# ADC3_10M.net
KiCad netlist of a schematic drawn in EAGLE
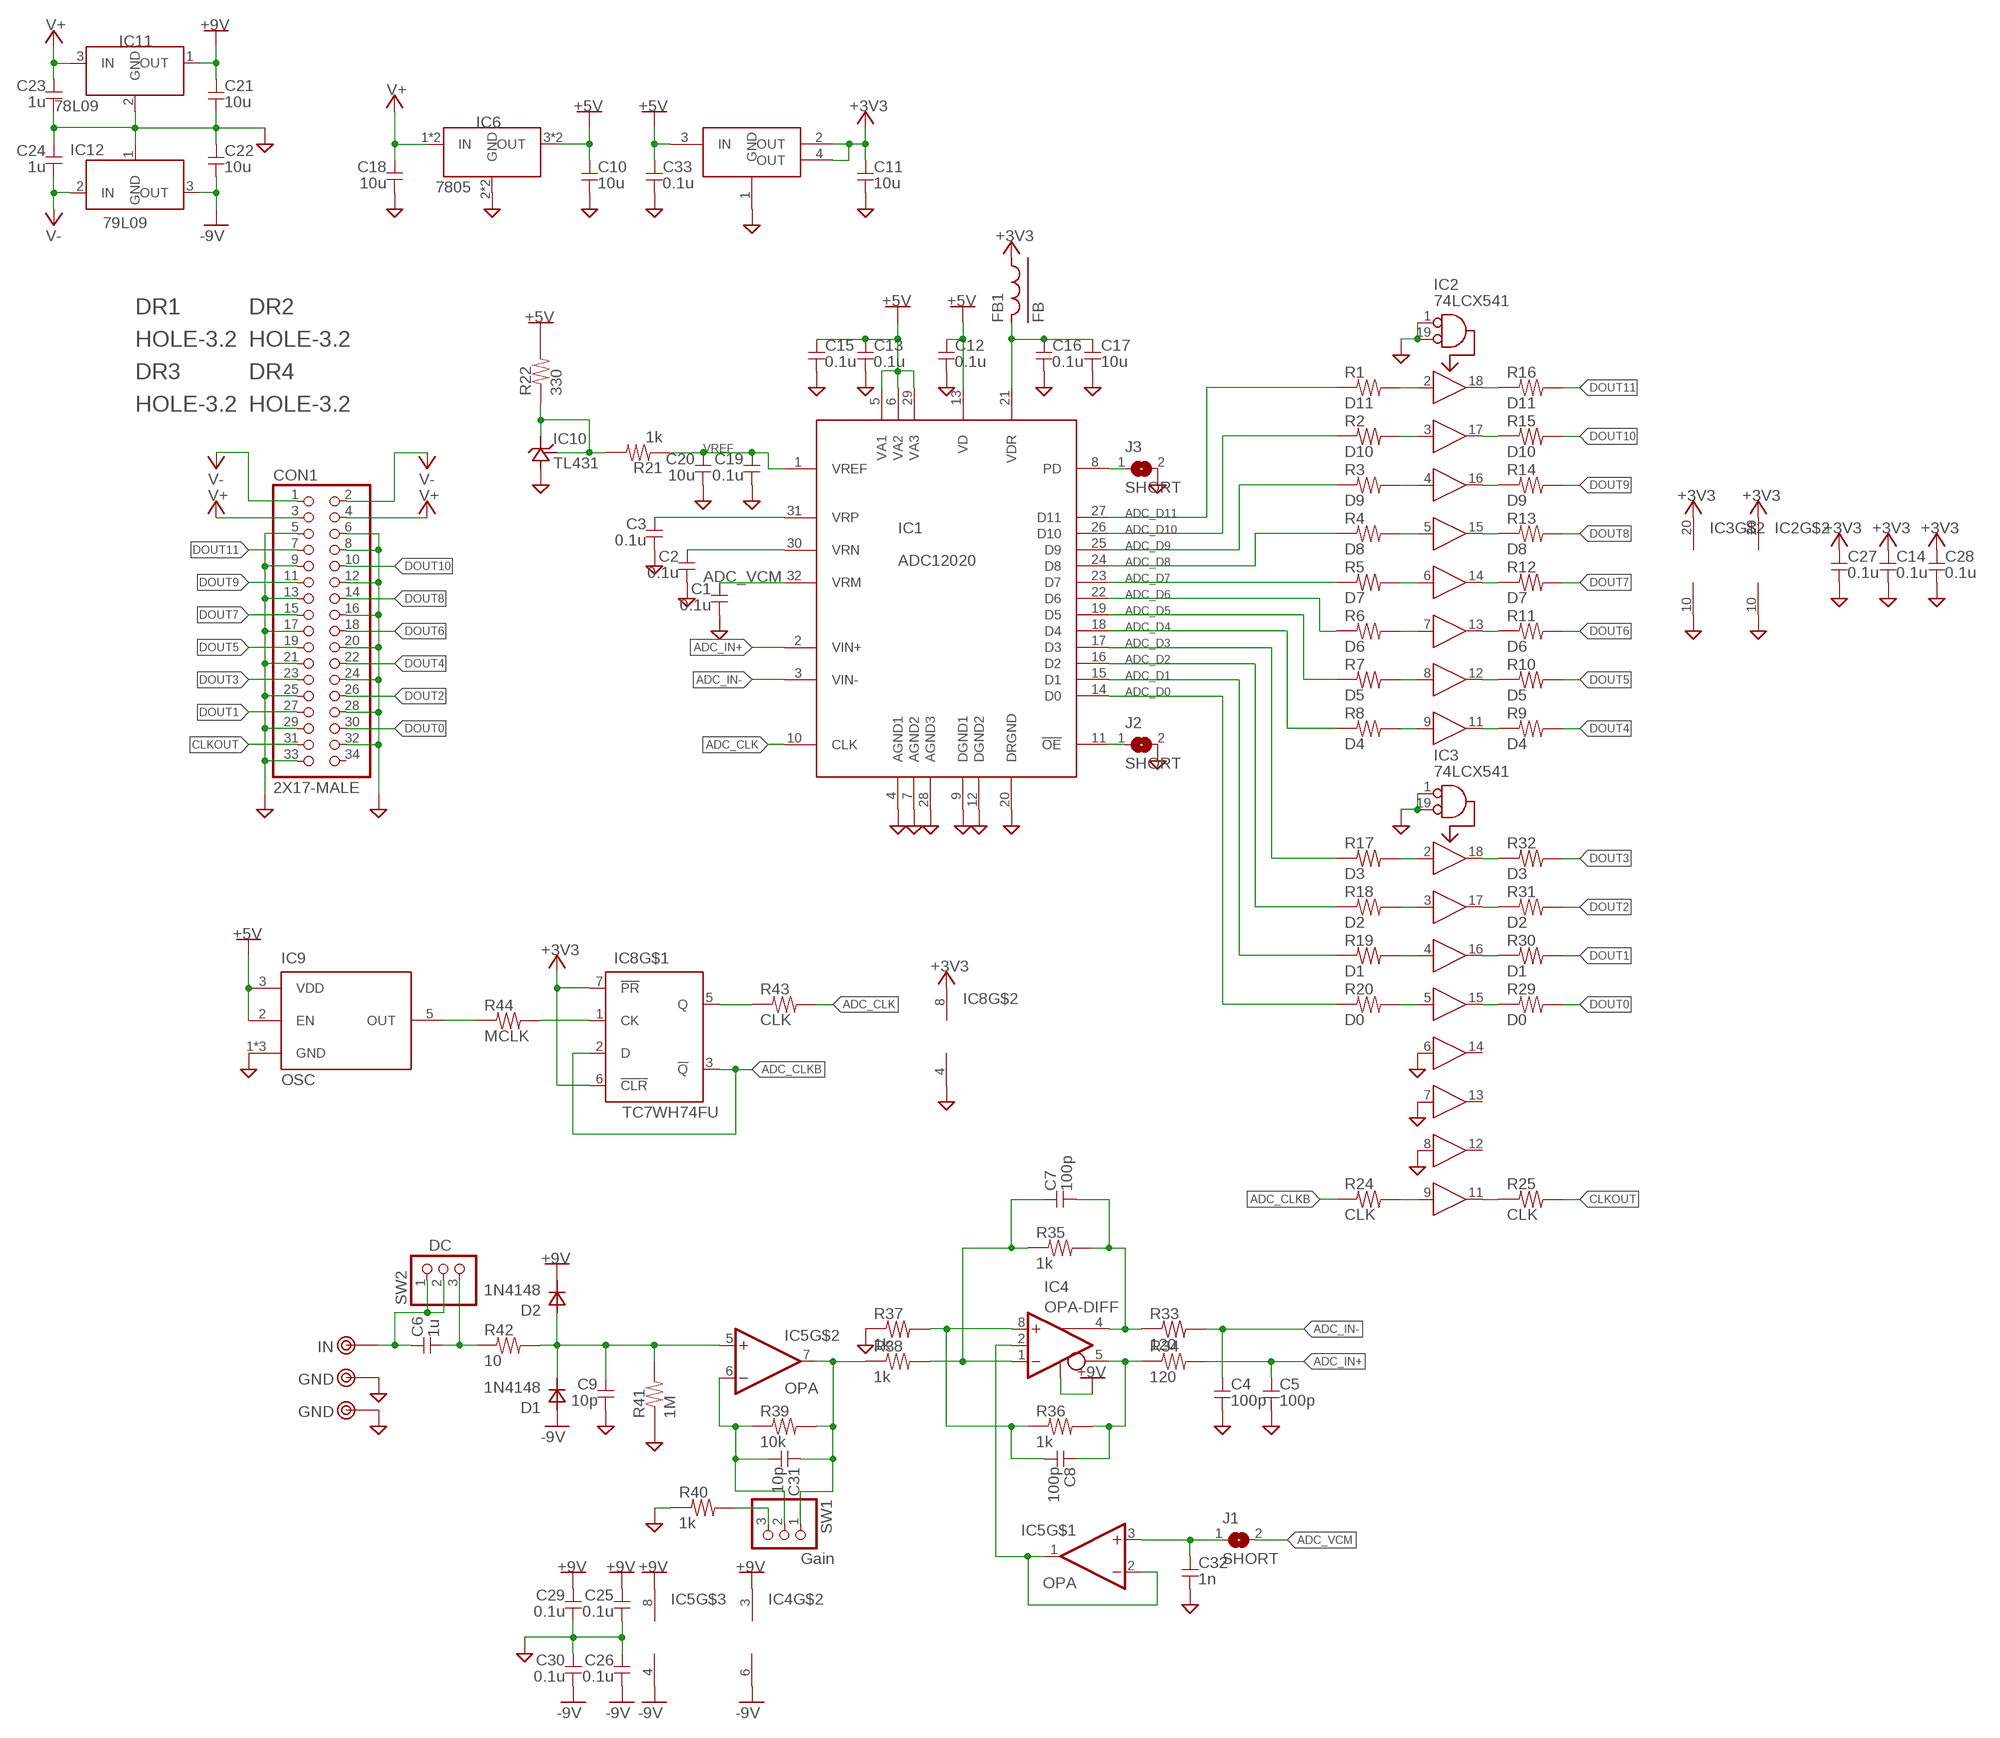
[diagram p0: schematic, sheet 1]

(export (version "E")
  (design (tool "Eeschema 10.0.6"))
  (components
    (comp (ref "C1")
      (value "0.1u")
      (footprint "eagle-import:1608")
      (libsource (lib "eagle-import") (part "C-1608"))
    )
    (comp (ref "C2")
      (value "0.1u")
      (footprint "eagle-import:1608")
      (libsource (lib "eagle-import") (part "C-1608"))
    )
    (comp (ref "C3")
      (value "0.1u")
      (footprint "eagle-import:1608")
      (libsource (lib "eagle-import") (part "C-1608"))
    )
    (comp (ref "C4")
      (value "100p")
      (footprint "eagle-import:1608")
      (libsource (lib "eagle-import") (part "C-1608"))
    )
    (comp (ref "C5")
      (value "100p")
      (footprint "eagle-import:1608")
      (libsource (lib "eagle-import") (part "C-1608"))
    )
    (comp (ref "C6")
      (value "1u")
      (footprint "eagle-import:C050")
      (libsource (lib "eagle-import") (part "C-5"))
    )
    (comp (ref "C7")
      (value "100p")
      (footprint "eagle-import:1608")
      (libsource (lib "eagle-import") (part "C-1608"))
    )
    (comp (ref "C8")
      (value "100p")
      (footprint "eagle-import:1608")
      (libsource (lib "eagle-import") (part "C-1608"))
    )
    (comp (ref "C9")
      (value "10p")
      (footprint "eagle-import:1608")
      (libsource (lib "eagle-import") (part "C-1608"))
    )
    (comp (ref "C10")
      (value "10u")
      (footprint "eagle-import:3216")
      (libsource (lib "eagle-import") (part "C-3216"))
    )
    (comp (ref "C11")
      (value "10u")
      (footprint "eagle-import:3216")
      (libsource (lib "eagle-import") (part "C-3216"))
    )
    (comp (ref "C12")
      (value "0.1u")
      (footprint "eagle-import:1608")
      (libsource (lib "eagle-import") (part "C-1608"))
    )
    (comp (ref "C13")
      (value "0.1u")
      (footprint "eagle-import:1608")
      (libsource (lib "eagle-import") (part "C-1608"))
    )
    (comp (ref "C14")
      (value "0.1u")
      (footprint "eagle-import:1608")
      (libsource (lib "eagle-import") (part "C-1608"))
    )
    (comp (ref "C15")
      (value "0.1u")
      (footprint "eagle-import:1608")
      (libsource (lib "eagle-import") (part "C-1608"))
    )
    (comp (ref "C16")
      (value "0.1u")
      (footprint "eagle-import:1608")
      (libsource (lib "eagle-import") (part "C-1608"))
    )
    (comp (ref "C17")
      (value "10u")
      (footprint "eagle-import:2012")
      (libsource (lib "eagle-import") (part "C-2012"))
    )
    (comp (ref "C18")
      (value "10u")
      (footprint "eagle-import:3216")
      (libsource (lib "eagle-import") (part "C-3216"))
    )
    (comp (ref "C19")
      (value "0.1u")
      (footprint "eagle-import:1608")
      (libsource (lib "eagle-import") (part "C-1608"))
    )
    (comp (ref "C20")
      (value "10u")
      (footprint "eagle-import:3216")
      (libsource (lib "eagle-import") (part "C-3216"))
    )
    (comp (ref "C21")
      (value "10u")
      (footprint "eagle-import:2012")
      (libsource (lib "eagle-import") (part "C-2012"))
    )
    (comp (ref "C22")
      (value "10u")
      (footprint "eagle-import:2012")
      (libsource (lib "eagle-import") (part "C-2012"))
    )
    (comp (ref "C23")
      (value "1u")
      (footprint "eagle-import:1608")
      (libsource (lib "eagle-import") (part "C-1608"))
    )
    (comp (ref "C24")
      (value "1u")
      (footprint "eagle-import:1608")
      (libsource (lib "eagle-import") (part "C-1608"))
    )
    (comp (ref "C25")
      (value "0.1u")
      (footprint "eagle-import:1608")
      (libsource (lib "eagle-import") (part "C-1608"))
    )
    (comp (ref "C26")
      (value "0.1u")
      (footprint "eagle-import:1608")
      (libsource (lib "eagle-import") (part "C-1608"))
    )
    (comp (ref "C27")
      (value "0.1u")
      (footprint "eagle-import:1608")
      (libsource (lib "eagle-import") (part "C-1608"))
    )
    (comp (ref "C28")
      (value "0.1u")
      (footprint "eagle-import:1608")
      (libsource (lib "eagle-import") (part "C-1608"))
    )
    (comp (ref "C29")
      (value "0.1u")
      (footprint "eagle-import:1608")
      (libsource (lib "eagle-import") (part "C-1608"))
    )
    (comp (ref "C30")
      (value "0.1u")
      (footprint "eagle-import:1608")
      (libsource (lib "eagle-import") (part "C-1608"))
    )
    (comp (ref "C31")
      (value "10p")
      (footprint "eagle-import:1608")
      (libsource (lib "eagle-import") (part "C-1608"))
    )
    (comp (ref "C32")
      (value "1n")
      (footprint "eagle-import:1608")
      (libsource (lib "eagle-import") (part "C-1608"))
    )
    (comp (ref "C33")
      (value "0.1u")
      (footprint "eagle-import:1608")
      (libsource (lib "eagle-import") (part "C-1608"))
    )
    (comp (ref "CON1")
      (value "2X17-MALE")
      (footprint "eagle-import:2X17_90-SWAPPED")
      (libsource (lib "eagle-import") (part "2X17-MALE"))
    )
    (comp (ref "D1")
      (value "1N4148")
      (footprint "eagle-import:SOD123")
      (libsource (lib "eagle-import") (part "DIODE-1N4148W"))
    )
    (comp (ref "D2")
      (value "1N4148")
      (footprint "eagle-import:SOD123")
      (libsource (lib "eagle-import") (part "DIODE-1N4148W"))
    )
    (comp (ref "DR1")
      (value "HOLE-3.2")
      (footprint "eagle-import:HOLE_3.2")
      (libsource (lib "eagle-import") (part "HOLE-3.2"))
    )
    (comp (ref "DR2")
      (value "HOLE-3.2")
      (footprint "eagle-import:HOLE_3.2")
      (libsource (lib "eagle-import") (part "HOLE-3.2"))
    )
    (comp (ref "DR3")
      (value "HOLE-3.2")
      (footprint "eagle-import:HOLE_3.2")
      (libsource (lib "eagle-import") (part "HOLE-3.2"))
    )
    (comp (ref "DR4")
      (value "HOLE-3.2")
      (footprint "eagle-import:HOLE_3.2")
      (libsource (lib "eagle-import") (part "HOLE-3.2"))
    )
    (comp (ref "FB1")
      (value "FB")
      (footprint "eagle-import:1608-J")
      (libsource (lib "eagle-import") (part "FB"))
    )
    (comp (ref "IC1")
      (value "ADC12020")
      (footprint "eagle-import:TQFP32-08")
      (libsource (lib "eagle-import") (part "ADC12020"))
    )
    (comp (ref "IC2")
      (value "74LCX541")
      (footprint "eagle-import:TSSOP20")
      (libsource (lib "eagle-import") (part "74LCX541"))
    )
    (comp (ref "IC3")
      (value "74LCX541")
      (footprint "eagle-import:TSSOP20")
      (libsource (lib "eagle-import") (part "74LCX541"))
    )
    (comp (ref "IC4")
      (value "OPA-DIFF")
      (footprint "eagle-import:SOP8")
      (libsource (lib "eagle-import") (part "OPA-DIFF"))
    )
    (comp (ref "IC5")
      (value "OPA")
      (footprint "eagle-import:SOP8")
      (libsource (lib "eagle-import") (part "OPA-2-SOP"))
    )
    (comp (ref "IC6")
      (value "7805")
      (footprint "eagle-import:TO220-SOP-DUAL")
      (libsource (lib "eagle-import") (part "78X-3"))
    )
    (comp (ref "IC7")
      (value "AZ1086H-3.3")
      (footprint "eagle-import:SOT223")
      (libsource (lib "eagle-import") (part "AZ1086?-H3.3"))
    )
    (comp (ref "IC8")
      (value "TC7WH74FU")
      (footprint "eagle-import:SSOP8-P-0.65")
      (libsource (lib "eagle-import") (part "TC7WH74FU"))
    )
    (comp (ref "IC9")
      (value "OSC")
      (footprint "eagle-import:MY_OSC")
      (libsource (lib "eagle-import") (part "OSC"))
    )
    (comp (ref "IC10")
      (value "TL431")
      (footprint "eagle-import:TO-92")
      (libsource (lib "eagle-import") (part "TL431"))
    )
    (comp (ref "IC11")
      (value "78L09")
      (footprint "eagle-import:TO-92")
      (libsource (lib "eagle-import") (part "78LX"))
    )
    (comp (ref "IC12")
      (value "79L09")
      (footprint "eagle-import:TO-92")
      (libsource (lib "eagle-import") (part "79LX"))
    )
    (comp (ref "J1")
      (value "SHORT")
      (footprint "eagle-import:1608-J")
      (libsource (lib "eagle-import") (part "SJ-1608"))
    )
    (comp (ref "J2")
      (value "SHORT")
      (footprint "eagle-import:1608-J")
      (libsource (lib "eagle-import") (part "SJ-1608"))
    )
    (comp (ref "J3")
      (value "SHORT")
      (footprint "eagle-import:1608-J")
      (libsource (lib "eagle-import") (part "SJ-1608"))
    )
    (comp (ref "R1")
      (value "D11")
      (footprint "eagle-import:1608-J")
      (libsource (lib "eagle-import") (part "R-1608J"))
    )
    (comp (ref "R2")
      (value "D10")
      (footprint "eagle-import:1608-J")
      (libsource (lib "eagle-import") (part "R-1608J"))
    )
    (comp (ref "R3")
      (value "D9")
      (footprint "eagle-import:1608-J")
      (libsource (lib "eagle-import") (part "R-1608J"))
    )
    (comp (ref "R4")
      (value "D8")
      (footprint "eagle-import:1608-J")
      (libsource (lib "eagle-import") (part "R-1608J"))
    )
    (comp (ref "R5")
      (value "D7")
      (footprint "eagle-import:1608-J")
      (libsource (lib "eagle-import") (part "R-1608J"))
    )
    (comp (ref "R6")
      (value "D6")
      (footprint "eagle-import:1608-J")
      (libsource (lib "eagle-import") (part "R-1608J"))
    )
    (comp (ref "R7")
      (value "D5")
      (footprint "eagle-import:1608-J")
      (libsource (lib "eagle-import") (part "R-1608J"))
    )
    (comp (ref "R8")
      (value "D4")
      (footprint "eagle-import:1608-J")
      (libsource (lib "eagle-import") (part "R-1608J"))
    )
    (comp (ref "R9")
      (value "D4")
      (footprint "eagle-import:1608-J")
      (libsource (lib "eagle-import") (part "R-1608J"))
    )
    (comp (ref "R10")
      (value "D5")
      (footprint "eagle-import:1608-J")
      (libsource (lib "eagle-import") (part "R-1608J"))
    )
    (comp (ref "R11")
      (value "D6")
      (footprint "eagle-import:1608-J")
      (libsource (lib "eagle-import") (part "R-1608J"))
    )
    (comp (ref "R12")
      (value "D7")
      (footprint "eagle-import:1608-J")
      (libsource (lib "eagle-import") (part "R-1608J"))
    )
    (comp (ref "R13")
      (value "D8")
      (footprint "eagle-import:1608-J")
      (libsource (lib "eagle-import") (part "R-1608J"))
    )
    (comp (ref "R14")
      (value "D9")
      (footprint "eagle-import:1608-J")
      (libsource (lib "eagle-import") (part "R-1608J"))
    )
    (comp (ref "R15")
      (value "D10")
      (footprint "eagle-import:1608-J")
      (libsource (lib "eagle-import") (part "R-1608J"))
    )
    (comp (ref "R16")
      (value "D11")
      (footprint "eagle-import:1608-J")
      (libsource (lib "eagle-import") (part "R-1608J"))
    )
    (comp (ref "R17")
      (value "D3")
      (footprint "eagle-import:1608-J")
      (libsource (lib "eagle-import") (part "R-1608J"))
    )
    (comp (ref "R18")
      (value "D2")
      (footprint "eagle-import:1608-J")
      (libsource (lib "eagle-import") (part "R-1608J"))
    )
    (comp (ref "R19")
      (value "D1")
      (footprint "eagle-import:1608-J")
      (libsource (lib "eagle-import") (part "R-1608J"))
    )
    (comp (ref "R20")
      (value "D0")
      (footprint "eagle-import:1608-J")
      (libsource (lib "eagle-import") (part "R-1608J"))
    )
    (comp (ref "R21")
      (value "1k")
      (footprint "eagle-import:1608")
      (libsource (lib "eagle-import") (part "R-1608"))
    )
    (comp (ref "R22")
      (value "330")
      (footprint "eagle-import:1608")
      (libsource (lib "eagle-import") (part "R-1608"))
    )
    (comp (ref "R24")
      (value "CLK")
      (footprint "eagle-import:1608-J")
      (libsource (lib "eagle-import") (part "R-1608J"))
    )
    (comp (ref "R25")
      (value "CLK")
      (footprint "eagle-import:1608-J")
      (libsource (lib "eagle-import") (part "R-1608J"))
    )
    (comp (ref "R29")
      (value "D0")
      (footprint "eagle-import:1608-J")
      (libsource (lib "eagle-import") (part "R-1608J"))
    )
    (comp (ref "R30")
      (value "D1")
      (footprint "eagle-import:1608-J")
      (libsource (lib "eagle-import") (part "R-1608J"))
    )
    (comp (ref "R31")
      (value "D2")
      (footprint "eagle-import:1608-J")
      (libsource (lib "eagle-import") (part "R-1608J"))
    )
    (comp (ref "R32")
      (value "D3")
      (footprint "eagle-import:1608-J")
      (libsource (lib "eagle-import") (part "R-1608J"))
    )
    (comp (ref "R33")
      (value "120")
      (footprint "eagle-import:1608")
      (libsource (lib "eagle-import") (part "R-1608"))
    )
    (comp (ref "R34")
      (value "120")
      (footprint "eagle-import:1608")
      (libsource (lib "eagle-import") (part "R-1608"))
    )
    (comp (ref "R35")
      (value "1k")
      (footprint "eagle-import:1608")
      (libsource (lib "eagle-import") (part "R-1608"))
    )
    (comp (ref "R36")
      (value "1k")
      (footprint "eagle-import:1608")
      (libsource (lib "eagle-import") (part "R-1608"))
    )
    (comp (ref "R37")
      (value "1k")
      (footprint "eagle-import:1608")
      (libsource (lib "eagle-import") (part "R-1608"))
    )
    (comp (ref "R38")
      (value "1k")
      (footprint "eagle-import:1608")
      (libsource (lib "eagle-import") (part "R-1608"))
    )
    (comp (ref "R39")
      (value "10k")
      (footprint "eagle-import:1608")
      (libsource (lib "eagle-import") (part "R-1608"))
    )
    (comp (ref "R40")
      (value "1k")
      (footprint "eagle-import:1608")
      (libsource (lib "eagle-import") (part "R-1608"))
    )
    (comp (ref "R41")
      (value "1M")
      (footprint "eagle-import:1608")
      (libsource (lib "eagle-import") (part "R-1608"))
    )
    (comp (ref "R42")
      (value "10")
      (footprint "eagle-import:1608")
      (libsource (lib "eagle-import") (part "R-1608"))
    )
    (comp (ref "R43")
      (value "CLK")
      (footprint "eagle-import:1608-J")
      (libsource (lib "eagle-import") (part "R-1608J"))
    )
    (comp (ref "R44")
      (value "MCLK")
      (footprint "eagle-import:1608-J")
      (libsource (lib "eagle-import") (part "R-1608J"))
    )
    (comp (ref "SW1")
      (value "Gain")
      (footprint "eagle-import:1X03")
      (libsource (lib "eagle-import") (part "SW-1X3"))
    )
    (comp (ref "SW2")
      (value "DC")
      (footprint "eagle-import:1X03")
      (libsource (lib "eagle-import") (part "SW-1X3"))
    )
    (comp (ref "TP1")
      (value "IN")
      (footprint "eagle-import:TESTPIN")
      (libsource (lib "eagle-import") (part "TESTPIN"))
    )
    (comp (ref "TP2")
      (value "GND")
      (footprint "eagle-import:TESTPIN")
      (libsource (lib "eagle-import") (part "TESTPIN"))
    )
    (comp (ref "TP3")
      (value "GND")
      (footprint "eagle-import:TESTPIN")
      (libsource (lib "eagle-import") (part "TESTPIN"))
    )
  )
  (nets
    (net (code "1") (name "+3V3") (class "Default")
      (node (ref "C11") (pin "1") (pinfunction "1_1") (pintype "passive"))
      (node (ref "C14") (pin "1") (pinfunction "1_1") (pintype "passive"))
      (node (ref "C27") (pin "1") (pinfunction "1_1") (pintype "passive"))
      (node (ref "C28") (pin "1") (pinfunction "1_1") (pintype "passive"))
      (node (ref "FB1") (pin "1") (pinfunction "1_1") (pintype "passive"))
      (node (ref "IC2") (pin "20") (pinfunction "V+_20") (pintype "power_in"))
      (node (ref "IC3") (pin "20") (pinfunction "V+_20") (pintype "power_in"))
      (node (ref "IC7") (pin "2") (pinfunction "OUT_2") (pintype "power_in"))
      (node (ref "IC7") (pin "4") (pinfunction "OUT_4") (pintype "power_in"))
      (node (ref "IC8") (pin "6") (pinfunction "~{CLR}_6") (pintype "input"))
      (node (ref "IC8") (pin "7") (pinfunction "~{PR}_7") (pintype "input"))
      (node (ref "IC8") (pin "8") (pinfunction "V+_8") (pintype "power_in"))
    )
    (net (code "2") (name "+5V") (class "Default")
      (node (ref "C10") (pin "1") (pinfunction "1_1") (pintype "passive"))
      (node (ref "C12") (pin "1") (pinfunction "1_1") (pintype "passive"))
      (node (ref "C13") (pin "1") (pinfunction "1_1") (pintype "passive"))
      (node (ref "C15") (pin "1") (pinfunction "1_1") (pintype "passive"))
      (node (ref "C33") (pin "1") (pinfunction "1_1") (pintype "passive"))
      (node (ref "IC1") (pin "13") (pinfunction "VD_13") (pintype "power_in"))
      (node (ref "IC1") (pin "29") (pinfunction "VA3_29") (pintype "power_in"))
      (node (ref "IC1") (pin "5") (pinfunction "VA1_5") (pintype "power_in"))
      (node (ref "IC1") (pin "6") (pinfunction "VA2_6") (pintype "power_in"))
      (node (ref "IC6") (pin "3") (pinfunction "OUT_3") (pintype "output"))
      (node (ref "IC6") (pin "6") (pinfunction "OUT_6") (pintype "output"))
      (node (ref "IC7") (pin "3") (pinfunction "IN_3") (pintype "power_in"))
      (node (ref "IC9") (pin "2") (pinfunction "EN_2") (pintype "passive"))
      (node (ref "IC9") (pin "3") (pinfunction "VDD_3") (pintype "power_in"))
      (node (ref "R22") (pin "2") (pinfunction "2_2") (pintype "passive"))
    )
    (net (code "3") (name "+9V") (class "Default")
      (node (ref "C21") (pin "1") (pinfunction "1_1") (pintype "passive"))
      (node (ref "C25") (pin "1") (pinfunction "1_1") (pintype "passive"))
      (node (ref "C29") (pin "1") (pinfunction "1_1") (pintype "passive"))
      (node (ref "D2") (pin "2") (pinfunction "K_2") (pintype "passive"))
      (node (ref "IC11") (pin "1") (pinfunction "OUT_1") (pintype "output"))
      (node (ref "IC4") (pin "3") (pinfunction "V+_3") (pintype "power_in"))
      (node (ref "IC4") (pin "7") (pinfunction "EN_7") (pintype "bidirectional"))
      (node (ref "IC5") (pin "8") (pinfunction "V+_8") (pintype "power_in"))
    )
    (net (code "4") (name "-9V") (class "Default")
      (node (ref "C22") (pin "2") (pinfunction "2_2") (pintype "passive"))
      (node (ref "C26") (pin "2") (pinfunction "2_2") (pintype "passive"))
      (node (ref "C30") (pin "2") (pinfunction "2_2") (pintype "passive"))
      (node (ref "D1") (pin "1") (pinfunction "A_1") (pintype "passive"))
      (node (ref "IC12") (pin "3") (pinfunction "OUT_3") (pintype "output"))
      (node (ref "IC4") (pin "6") (pinfunction "V-_6") (pintype "power_in"))
      (node (ref "IC5") (pin "4") (pinfunction "V-_4") (pintype "power_in"))
    )
    (net (code "5") (name "/ADC_D0") (class "Default")
      (node (ref "IC1") (pin "14") (pinfunction "D0_14") (pintype "output"))
      (node (ref "R20") (pin "1") (pinfunction "1_1") (pintype "passive"))
    )
    (net (code "6") (name "/ADC_D1") (class "Default")
      (node (ref "IC1") (pin "15") (pinfunction "D1_15") (pintype "output"))
      (node (ref "R19") (pin "1") (pinfunction "1_1") (pintype "passive"))
    )
    (net (code "7") (name "/ADC_D2") (class "Default")
      (node (ref "IC1") (pin "16") (pinfunction "D2_16") (pintype "output"))
      (node (ref "R18") (pin "1") (pinfunction "1_1") (pintype "passive"))
    )
    (net (code "8") (name "/ADC_D3") (class "Default")
      (node (ref "IC1") (pin "17") (pinfunction "D3_17") (pintype "output"))
      (node (ref "R17") (pin "1") (pinfunction "1_1") (pintype "passive"))
    )
    (net (code "9") (name "/ADC_D4") (class "Default")
      (node (ref "IC1") (pin "18") (pinfunction "D4_18") (pintype "output"))
      (node (ref "R8") (pin "1") (pinfunction "1_1") (pintype "passive"))
    )
    (net (code "10") (name "/ADC_D5") (class "Default")
      (node (ref "IC1") (pin "19") (pinfunction "D5_19") (pintype "output"))
      (node (ref "R7") (pin "1") (pinfunction "1_1") (pintype "passive"))
    )
    (net (code "11") (name "/ADC_D6") (class "Default")
      (node (ref "IC1") (pin "22") (pinfunction "D6_22") (pintype "output"))
      (node (ref "R6") (pin "1") (pinfunction "1_1") (pintype "passive"))
    )
    (net (code "12") (name "/ADC_D7") (class "Default")
      (node (ref "IC1") (pin "23") (pinfunction "D7_23") (pintype "output"))
      (node (ref "R5") (pin "1") (pinfunction "1_1") (pintype "passive"))
    )
    (net (code "13") (name "/ADC_D8") (class "Default")
      (node (ref "IC1") (pin "24") (pinfunction "D8_24") (pintype "output"))
      (node (ref "R4") (pin "1") (pinfunction "1_1") (pintype "passive"))
    )
    (net (code "14") (name "/ADC_D9") (class "Default")
      (node (ref "IC1") (pin "25") (pinfunction "D9_25") (pintype "output"))
      (node (ref "R3") (pin "1") (pinfunction "1_1") (pintype "passive"))
    )
    (net (code "15") (name "/ADC_D10") (class "Default")
      (node (ref "IC1") (pin "26") (pinfunction "D10_26") (pintype "output"))
      (node (ref "R2") (pin "1") (pinfunction "1_1") (pintype "passive"))
    )
    (net (code "16") (name "/ADC_D11") (class "Default")
      (node (ref "IC1") (pin "27") (pinfunction "D11_27") (pintype "output"))
      (node (ref "R1") (pin "1") (pinfunction "1_1") (pintype "passive"))
    )
    (net (code "17") (name "/VREF") (class "Default")
      (node (ref "C19") (pin "1") (pinfunction "1_1") (pintype "passive"))
      (node (ref "C20") (pin "1") (pinfunction "1_1") (pintype "passive"))
      (node (ref "IC1") (pin "1") (pinfunction "VREF_1") (pintype "power_in"))
      (node (ref "R21") (pin "1") (pinfunction "1_1") (pintype "passive"))
    )
    (net (code "18") (name "ADC_CLK") (class "Default")
      (node (ref "IC1") (pin "10") (pinfunction "CLK_10") (pintype "input"))
      (node (ref "R43") (pin "2") (pinfunction "2_2") (pintype "passive"))
    )
    (net (code "19") (name "ADC_CLKB") (class "Default")
      (node (ref "IC8") (pin "2") (pinfunction "D_2") (pintype "input"))
      (node (ref "IC8") (pin "3") (pinfunction "~{Q}_3") (pintype "output"))
      (node (ref "R24") (pin "1") (pinfunction "1_1") (pintype "passive"))
    )
    (net (code "20") (name "ADC_IN+") (class "Default")
      (node (ref "C5") (pin "1") (pinfunction "1_1") (pintype "passive"))
      (node (ref "IC1") (pin "2") (pinfunction "VIN+_2") (pintype "input"))
      (node (ref "R34") (pin "2") (pinfunction "2_2") (pintype "passive"))
    )
    (net (code "21") (name "ADC_IN-") (class "Default")
      (node (ref "C4") (pin "1") (pinfunction "1_1") (pintype "passive"))
      (node (ref "IC1") (pin "3") (pinfunction "VIN-_3") (pintype "input"))
      (node (ref "R33") (pin "2") (pinfunction "2_2") (pintype "passive"))
    )
    (net (code "22") (name "ADC_VCM") (class "Default")
      (node (ref "C1") (pin "1") (pinfunction "1_1") (pintype "passive"))
      (node (ref "IC1") (pin "32") (pinfunction "VRM_32") (pintype "passive"))
      (node (ref "J1") (pin "2") (pinfunction "2_2") (pintype "passive"))
    )
    (net (code "23") (name "CLKOUT") (class "Default")
      (node (ref "CON1") (pin "31") (pinfunction "31_31") (pintype "passive"))
      (node (ref "R25") (pin "2") (pinfunction "2_2") (pintype "passive"))
    )
    (net (code "24") (name "DOUT0") (class "Default")
      (node (ref "CON1") (pin "30") (pinfunction "30_30") (pintype "passive"))
      (node (ref "R29") (pin "2") (pinfunction "2_2") (pintype "passive"))
    )
    (net (code "25") (name "DOUT1") (class "Default")
      (node (ref "CON1") (pin "27") (pinfunction "27_27") (pintype "passive"))
      (node (ref "R30") (pin "2") (pinfunction "2_2") (pintype "passive"))
    )
    (net (code "26") (name "DOUT2") (class "Default")
      (node (ref "CON1") (pin "26") (pinfunction "26_26") (pintype "passive"))
      (node (ref "R31") (pin "2") (pinfunction "2_2") (pintype "passive"))
    )
    (net (code "27") (name "DOUT3") (class "Default")
      (node (ref "CON1") (pin "23") (pinfunction "23_23") (pintype "passive"))
      (node (ref "R32") (pin "2") (pinfunction "2_2") (pintype "passive"))
    )
    (net (code "28") (name "DOUT4") (class "Default")
      (node (ref "CON1") (pin "22") (pinfunction "22_22") (pintype "passive"))
      (node (ref "R9") (pin "2") (pinfunction "2_2") (pintype "passive"))
    )
    (net (code "29") (name "DOUT5") (class "Default")
      (node (ref "CON1") (pin "19") (pinfunction "19_19") (pintype "passive"))
      (node (ref "R10") (pin "2") (pinfunction "2_2") (pintype "passive"))
    )
    (net (code "30") (name "DOUT6") (class "Default")
      (node (ref "CON1") (pin "18") (pinfunction "18_18") (pintype "passive"))
      (node (ref "R11") (pin "2") (pinfunction "2_2") (pintype "passive"))
    )
    (net (code "31") (name "DOUT7") (class "Default")
      (node (ref "CON1") (pin "15") (pinfunction "15_15") (pintype "passive"))
      (node (ref "R12") (pin "2") (pinfunction "2_2") (pintype "passive"))
    )
    (net (code "32") (name "DOUT8") (class "Default")
      (node (ref "CON1") (pin "14") (pinfunction "14_14") (pintype "passive"))
      (node (ref "R13") (pin "2") (pinfunction "2_2") (pintype "passive"))
    )
    (net (code "33") (name "DOUT9") (class "Default")
      (node (ref "CON1") (pin "11") (pinfunction "11_11") (pintype "passive"))
      (node (ref "R14") (pin "2") (pinfunction "2_2") (pintype "passive"))
    )
    (net (code "34") (name "DOUT10") (class "Default")
      (node (ref "CON1") (pin "10") (pinfunction "10_10") (pintype "passive"))
      (node (ref "R15") (pin "2") (pinfunction "2_2") (pintype "passive"))
    )
    (net (code "35") (name "DOUT11") (class "Default")
      (node (ref "CON1") (pin "7") (pinfunction "7_7") (pintype "passive"))
      (node (ref "R16") (pin "2") (pinfunction "2_2") (pintype "passive"))
    )
    (net (code "36") (name "GND") (class "Default")
      (node (ref "C1") (pin "2") (pinfunction "2_2") (pintype "passive"))
      (node (ref "C10") (pin "2") (pinfunction "2_2") (pintype "passive"))
      (node (ref "C11") (pin "2") (pinfunction "2_2") (pintype "passive"))
      (node (ref "C12") (pin "2") (pinfunction "2_2") (pintype "passive"))
      (node (ref "C13") (pin "2") (pinfunction "2_2") (pintype "passive"))
      (node (ref "C14") (pin "2") (pinfunction "2_2") (pintype "passive"))
      (node (ref "C15") (pin "2") (pinfunction "2_2") (pintype "passive"))
      (node (ref "C16") (pin "2") (pinfunction "2_2") (pintype "passive"))
      (node (ref "C17") (pin "2") (pinfunction "2_2") (pintype "passive"))
      (node (ref "C18") (pin "2") (pinfunction "2_2") (pintype "passive"))
      (node (ref "C19") (pin "2") (pinfunction "2_2") (pintype "passive"))
      (node (ref "C2") (pin "2") (pinfunction "2_2") (pintype "passive"))
      (node (ref "C20") (pin "2") (pinfunction "2_2") (pintype "passive"))
      (node (ref "C21") (pin "2") (pinfunction "2_2") (pintype "passive"))
      (node (ref "C22") (pin "1") (pinfunction "1_1") (pintype "passive"))
      (node (ref "C23") (pin "2") (pinfunction "2_2") (pintype "passive"))
      (node (ref "C24") (pin "1") (pinfunction "1_1") (pintype "passive"))
      (node (ref "C25") (pin "2") (pinfunction "2_2") (pintype "passive"))
      (node (ref "C26") (pin "1") (pinfunction "1_1") (pintype "passive"))
      (node (ref "C27") (pin "2") (pinfunction "2_2") (pintype "passive"))
      (node (ref "C28") (pin "2") (pinfunction "2_2") (pintype "passive"))
      (node (ref "C29") (pin "2") (pinfunction "2_2") (pintype "passive"))
      (node (ref "C3") (pin "2") (pinfunction "2_2") (pintype "passive"))
      (node (ref "C30") (pin "1") (pinfunction "1_1") (pintype "passive"))
      (node (ref "C32") (pin "2") (pinfunction "2_2") (pintype "passive"))
      (node (ref "C33") (pin "2") (pinfunction "2_2") (pintype "passive"))
      (node (ref "C4") (pin "2") (pinfunction "2_2") (pintype "passive"))
      (node (ref "C5") (pin "2") (pinfunction "2_2") (pintype "passive"))
      (node (ref "C9") (pin "2") (pinfunction "2_2") (pintype "passive"))
      (node (ref "CON1") (pin "12") (pinfunction "12_12") (pintype "passive"))
      (node (ref "CON1") (pin "13") (pinfunction "13_13") (pintype "passive"))
      (node (ref "CON1") (pin "16") (pinfunction "16_16") (pintype "passive"))
      (node (ref "CON1") (pin "17") (pinfunction "17_17") (pintype "passive"))
      (node (ref "CON1") (pin "20") (pinfunction "20_20") (pintype "passive"))
      (node (ref "CON1") (pin "21") (pinfunction "21_21") (pintype "passive"))
      (node (ref "CON1") (pin "24") (pinfunction "24_24") (pintype "passive"))
      (node (ref "CON1") (pin "25") (pinfunction "25_25") (pintype "passive"))
      (node (ref "CON1") (pin "28") (pinfunction "28_28") (pintype "passive"))
      (node (ref "CON1") (pin "29") (pinfunction "29_29") (pintype "passive"))
      (node (ref "CON1") (pin "32") (pinfunction "32_32") (pintype "passive"))
      (node (ref "CON1") (pin "33") (pinfunction "33_33") (pintype "passive"))
      (node (ref "CON1") (pin "5") (pinfunction "5_5") (pintype "passive"))
      (node (ref "CON1") (pin "6") (pinfunction "6_6") (pintype "passive"))
      (node (ref "CON1") (pin "8") (pinfunction "8_8") (pintype "passive"))
      (node (ref "CON1") (pin "9") (pinfunction "9_9") (pintype "passive"))
      (node (ref "IC1") (pin "12") (pinfunction "DGND2_12") (pintype "power_in"))
      (node (ref "IC1") (pin "20") (pinfunction "DRGND_20") (pintype "power_in"))
      (node (ref "IC1") (pin "28") (pinfunction "AGND3_28") (pintype "power_in"))
      (node (ref "IC1") (pin "4") (pinfunction "AGND1_4") (pintype "power_in"))
      (node (ref "IC1") (pin "7") (pinfunction "AGND2_7") (pintype "power_in"))
      (node (ref "IC1") (pin "9") (pinfunction "DGND1_9") (pintype "power_in"))
      (node (ref "IC10") (pin "2") (pinfunction "GND_2") (pintype "bidirectional"))
      (node (ref "IC11") (pin "2") (pinfunction "GND_2") (pintype "power_in"))
      (node (ref "IC12") (pin "1") (pinfunction "GND_1") (pintype "input"))
      (node (ref "IC2") (pin "1") (pinfunction "~{OE1}_1") (pintype "input"))
      (node (ref "IC2") (pin "10") (pinfunction "V-_10") (pintype "power_in"))
      (node (ref "IC2") (pin "19") (pinfunction "~{OE2}_19") (pintype "input"))
      (node (ref "IC3") (pin "1") (pinfunction "~{OE1}_1") (pintype "input"))
      (node (ref "IC3") (pin "10") (pinfunction "V-_10") (pintype "power_in"))
      (node (ref "IC3") (pin "19") (pinfunction "~{OE2}_19") (pintype "input"))
      (node (ref "IC3") (pin "6") (pinfunction "IN5_6") (pintype "input"))
      (node (ref "IC3") (pin "7") (pinfunction "IN6_7") (pintype "input"))
      (node (ref "IC3") (pin "8") (pinfunction "IN7_8") (pintype "input"))
      (node (ref "IC6") (pin "2") (pinfunction "GND_2") (pintype "power_in"))
      (node (ref "IC6") (pin "5") (pinfunction "GND_5") (pintype "power_in"))
      (node (ref "IC7") (pin "1") (pinfunction "GND_1") (pintype "power_in"))
      (node (ref "IC8") (pin "4") (pinfunction "V-_4") (pintype "power_in"))
      (node (ref "IC9") (pin "1") (pinfunction "GND_1") (pintype "passive"))
      (node (ref "IC9") (pin "4") (pinfunction "GND_4") (pintype "passive"))
      (node (ref "IC9") (pin "6") (pinfunction "GND_6") (pintype "passive"))
      (node (ref "J2") (pin "2") (pinfunction "2_2") (pintype "passive"))
      (node (ref "J3") (pin "2") (pinfunction "2_2") (pintype "passive"))
      (node (ref "R37") (pin "1") (pinfunction "1_1") (pintype "passive"))
      (node (ref "R40") (pin "1") (pinfunction "1_1") (pintype "passive"))
      (node (ref "R41") (pin "1") (pinfunction "1_1") (pintype "passive"))
      (node (ref "TP2") (pin "1") (pinfunction "1_1") (pintype "passive"))
      (node (ref "TP3") (pin "1") (pinfunction "1_1") (pintype "passive"))
    )
    (net (code "37") (name "Net-(C6-Pad1)") (class "Default")
      (node (ref "C6") (pin "1") (pinfunction "1_1") (pintype "passive"))
      (node (ref "SW2") (pin "1") (pinfunction "1_1") (pintype "passive"))
      (node (ref "SW2") (pin "2") (pinfunction "2_2") (pintype "passive"))
      (node (ref "TP1") (pin "1") (pinfunction "1_1") (pintype "passive"))
    )
    (net (code "38") (name "Net-(C6-Pad2)") (class "Default")
      (node (ref "C6") (pin "2") (pinfunction "2_2") (pintype "passive"))
      (node (ref "R42") (pin "1") (pinfunction "1_1") (pintype "passive"))
      (node (ref "SW2") (pin "3") (pinfunction "3_3") (pintype "passive"))
    )
    (net (code "39") (name "Net-(D1-K)") (class "Default")
      (node (ref "C9") (pin "1") (pinfunction "1_1") (pintype "passive"))
      (node (ref "D1") (pin "2") (pinfunction "K_2") (pintype "passive"))
      (node (ref "D2") (pin "1") (pinfunction "A_1") (pintype "passive"))
      (node (ref "IC5") (pin "5") (pinfunction "+IN_5") (pintype "input"))
      (node (ref "R41") (pin "2") (pinfunction "2_2") (pintype "passive"))
      (node (ref "R42") (pin "2") (pinfunction "2_2") (pintype "passive"))
    )
    (net (code "40") (name "Net-(IC1-PD)") (class "Default")
      (node (ref "IC1") (pin "8") (pinfunction "PD_8") (pintype "input"))
      (node (ref "J3") (pin "1") (pinfunction "1_1") (pintype "passive"))
    )
    (net (code "41") (name "Net-(IC1-VDR)") (class "Default")
      (node (ref "C16") (pin "1") (pinfunction "1_1") (pintype "passive"))
      (node (ref "C17") (pin "1") (pinfunction "1_1") (pintype "passive"))
      (node (ref "FB1") (pin "2") (pinfunction "2_2") (pintype "passive"))
      (node (ref "IC1") (pin "21") (pinfunction "VDR_21") (pintype "power_in"))
    )
    (net (code "42") (name "Net-(IC1-VRN)") (class "Default")
      (node (ref "C2") (pin "1") (pinfunction "1_1") (pintype "passive"))
      (node (ref "IC1") (pin "30") (pinfunction "VRN_30") (pintype "passive"))
    )
    (net (code "43") (name "Net-(IC1-VRP)") (class "Default")
      (node (ref "C3") (pin "1") (pinfunction "1_1") (pintype "passive"))
      (node (ref "IC1") (pin "31") (pinfunction "VRP_31") (pintype "passive"))
    )
    (net (code "44") (name "Net-(IC1-~{OE})") (class "Default")
      (node (ref "IC1") (pin "11") (pinfunction "~{OE}_11") (pintype "input"))
      (node (ref "J2") (pin "1") (pinfunction "1_1") (pintype "passive"))
    )
    (net (code "45") (name "Net-(IC2A-IN1)") (class "Default")
      (node (ref "IC2") (pin "2") (pinfunction "IN1_2") (pintype "input"))
      (node (ref "R1") (pin "2") (pinfunction "2_2") (pintype "passive"))
    )
    (net (code "46") (name "Net-(IC2A-IN2)") (class "Default")
      (node (ref "IC2") (pin "3") (pinfunction "IN2_3") (pintype "input"))
      (node (ref "R2") (pin "2") (pinfunction "2_2") (pintype "passive"))
    )
    (net (code "47") (name "Net-(IC2A-IN3)") (class "Default")
      (node (ref "IC2") (pin "4") (pinfunction "IN3_4") (pintype "input"))
      (node (ref "R3") (pin "2") (pinfunction "2_2") (pintype "passive"))
    )
    (net (code "48") (name "Net-(IC2A-IN4)") (class "Default")
      (node (ref "IC2") (pin "5") (pinfunction "IN4_5") (pintype "input"))
      (node (ref "R4") (pin "2") (pinfunction "2_2") (pintype "passive"))
    )
    (net (code "49") (name "Net-(IC2A-IN5)") (class "Default")
      (node (ref "IC2") (pin "6") (pinfunction "IN5_6") (pintype "input"))
      (node (ref "R5") (pin "2") (pinfunction "2_2") (pintype "passive"))
    )
    (net (code "50") (name "Net-(IC2A-IN6)") (class "Default")
      (node (ref "IC2") (pin "7") (pinfunction "IN6_7") (pintype "input"))
      (node (ref "R6") (pin "2") (pinfunction "2_2") (pintype "passive"))
    )
    (net (code "51") (name "Net-(IC2A-IN7)") (class "Default")
      (node (ref "IC2") (pin "8") (pinfunction "IN7_8") (pintype "input"))
      (node (ref "R7") (pin "2") (pinfunction "2_2") (pintype "passive"))
    )
    (net (code "52") (name "Net-(IC2A-IN8)") (class "Default")
      (node (ref "IC2") (pin "9") (pinfunction "IN8_9") (pintype "input"))
      (node (ref "R8") (pin "2") (pinfunction "2_2") (pintype "passive"))
    )
    (net (code "53") (name "Net-(IC2A-OUT1)") (class "Default")
      (node (ref "IC2") (pin "18") (pinfunction "OUT1_18") (pintype "output"))
      (node (ref "R16") (pin "1") (pinfunction "1_1") (pintype "passive"))
    )
    (net (code "54") (name "Net-(IC2A-OUT2)") (class "Default")
      (node (ref "IC2") (pin "17") (pinfunction "OUT2_17") (pintype "output"))
      (node (ref "R15") (pin "1") (pinfunction "1_1") (pintype "passive"))
    )
    (net (code "55") (name "Net-(IC2A-OUT3)") (class "Default")
      (node (ref "IC2") (pin "16") (pinfunction "OUT3_16") (pintype "output"))
      (node (ref "R14") (pin "1") (pinfunction "1_1") (pintype "passive"))
    )
    (net (code "56") (name "Net-(IC2A-OUT4)") (class "Default")
      (node (ref "IC2") (pin "15") (pinfunction "OUT4_15") (pintype "output"))
      (node (ref "R13") (pin "1") (pinfunction "1_1") (pintype "passive"))
    )
    (net (code "57") (name "Net-(IC2A-OUT5)") (class "Default")
      (node (ref "IC2") (pin "14") (pinfunction "OUT5_14") (pintype "output"))
      (node (ref "R12") (pin "1") (pinfunction "1_1") (pintype "passive"))
    )
    (net (code "58") (name "Net-(IC2A-OUT6)") (class "Default")
      (node (ref "IC2") (pin "13") (pinfunction "OUT6_13") (pintype "output"))
      (node (ref "R11") (pin "1") (pinfunction "1_1") (pintype "passive"))
    )
    (net (code "59") (name "Net-(IC2A-OUT7)") (class "Default")
      (node (ref "IC2") (pin "12") (pinfunction "OUT7_12") (pintype "output"))
      (node (ref "R10") (pin "1") (pinfunction "1_1") (pintype "passive"))
    )
    (net (code "60") (name "Net-(IC2A-OUT8)") (class "Default")
      (node (ref "IC2") (pin "11") (pinfunction "OUT8_11") (pintype "output"))
      (node (ref "R9") (pin "1") (pinfunction "1_1") (pintype "passive"))
    )
    (net (code "61") (name "Net-(IC3A-IN1)") (class "Default")
      (node (ref "IC3") (pin "2") (pinfunction "IN1_2") (pintype "input"))
      (node (ref "R17") (pin "2") (pinfunction "2_2") (pintype "passive"))
    )
    (net (code "62") (name "Net-(IC3A-IN2)") (class "Default")
      (node (ref "IC3") (pin "3") (pinfunction "IN2_3") (pintype "input"))
      (node (ref "R18") (pin "2") (pinfunction "2_2") (pintype "passive"))
    )
    (net (code "63") (name "Net-(IC3A-IN3)") (class "Default")
      (node (ref "IC3") (pin "4") (pinfunction "IN3_4") (pintype "input"))
      (node (ref "R19") (pin "2") (pinfunction "2_2") (pintype "passive"))
    )
    (net (code "64") (name "Net-(IC3A-IN4)") (class "Default")
      (node (ref "IC3") (pin "5") (pinfunction "IN4_5") (pintype "input"))
      (node (ref "R20") (pin "2") (pinfunction "2_2") (pintype "passive"))
    )
    (net (code "65") (name "Net-(IC3A-IN8)") (class "Default")
      (node (ref "IC3") (pin "9") (pinfunction "IN8_9") (pintype "input"))
      (node (ref "R24") (pin "2") (pinfunction "2_2") (pintype "passive"))
    )
    (net (code "66") (name "Net-(IC3A-OUT1)") (class "Default")
      (node (ref "IC3") (pin "18") (pinfunction "OUT1_18") (pintype "output"))
      (node (ref "R32") (pin "1") (pinfunction "1_1") (pintype "passive"))
    )
    (net (code "67") (name "Net-(IC3A-OUT2)") (class "Default")
      (node (ref "IC3") (pin "17") (pinfunction "OUT2_17") (pintype "output"))
      (node (ref "R31") (pin "1") (pinfunction "1_1") (pintype "passive"))
    )
    (net (code "68") (name "Net-(IC3A-OUT3)") (class "Default")
      (node (ref "IC3") (pin "16") (pinfunction "OUT3_16") (pintype "output"))
      (node (ref "R30") (pin "1") (pinfunction "1_1") (pintype "passive"))
    )
    (net (code "69") (name "Net-(IC3A-OUT4)") (class "Default")
      (node (ref "IC3") (pin "15") (pinfunction "OUT4_15") (pintype "output"))
      (node (ref "R29") (pin "1") (pinfunction "1_1") (pintype "passive"))
    )
    (net (code "70") (name "Net-(IC3A-OUT8)") (class "Default")
      (node (ref "IC3") (pin "11") (pinfunction "OUT8_11") (pintype "output"))
      (node (ref "R25") (pin "1") (pinfunction "1_1") (pintype "passive"))
    )
    (net (code "71") (name "Net-(IC4A-+IN)") (class "Default")
      (node (ref "C8") (pin "2") (pinfunction "2_2") (pintype "passive"))
      (node (ref "IC4") (pin "8") (pinfunction "+IN_8") (pintype "input"))
      (node (ref "R36") (pin "1") (pinfunction "1_1") (pintype "passive"))
      (node (ref "R37") (pin "2") (pinfunction "2_2") (pintype "passive"))
    )
    (net (code "72") (name "Net-(IC4A-+OUT)") (class "Default")
      (node (ref "C7") (pin "2") (pinfunction "2_2") (pintype "passive"))
      (node (ref "IC4") (pin "4") (pinfunction "+OUT_4") (pintype "output"))
      (node (ref "R33") (pin "1") (pinfunction "1_1") (pintype "passive"))
      (node (ref "R35") (pin "2") (pinfunction "2_2") (pintype "passive"))
    )
    (net (code "73") (name "Net-(IC4A--IN)") (class "Default")
      (node (ref "C7") (pin "1") (pinfunction "1_1") (pintype "passive"))
      (node (ref "IC4") (pin "1") (pinfunction "-IN_1") (pintype "input"))
      (node (ref "R35") (pin "1") (pinfunction "1_1") (pintype "passive"))
      (node (ref "R38") (pin "2") (pinfunction "2_2") (pintype "passive"))
    )
    (net (code "74") (name "Net-(IC4A--OUT)") (class "Default")
      (node (ref "C8") (pin "1") (pinfunction "1_1") (pintype "passive"))
      (node (ref "IC4") (pin "5") (pinfunction "-OUT_5") (pintype "output"))
      (node (ref "R34") (pin "1") (pinfunction "1_1") (pintype "passive"))
      (node (ref "R36") (pin "2") (pinfunction "2_2") (pintype "passive"))
    )
    (net (code "75") (name "Net-(IC4A-CM)") (class "Default")
      (node (ref "IC4") (pin "2") (pinfunction "CM_2") (pintype "input"))
      (node (ref "IC5") (pin "1") (pinfunction "OUT_1") (pintype "output"))
      (node (ref "IC5") (pin "2") (pinfunction "-IN_2") (pintype "input"))
    )
    (net (code "76") (name "Net-(IC5A-+IN)") (class "Default")
      (node (ref "C32") (pin "1") (pinfunction "1_1") (pintype "passive"))
      (node (ref "IC5") (pin "3") (pinfunction "+IN_3") (pintype "input"))
      (node (ref "J1") (pin "1") (pinfunction "1_1") (pintype "passive"))
    )
    (net (code "77") (name "Net-(IC5B--IN)") (class "Default")
      (node (ref "C31") (pin "2") (pinfunction "2_2") (pintype "passive"))
      (node (ref "IC5") (pin "6") (pinfunction "-IN_6") (pintype "input"))
      (node (ref "R39") (pin "1") (pinfunction "1_1") (pintype "passive"))
      (node (ref "SW1") (pin "2") (pinfunction "2_2") (pintype "passive"))
    )
    (net (code "78") (name "Net-(IC5B-OUT)") (class "Default")
      (node (ref "C31") (pin "1") (pinfunction "1_1") (pintype "passive"))
      (node (ref "IC5") (pin "7") (pinfunction "OUT_7") (pintype "output"))
      (node (ref "R38") (pin "1") (pinfunction "1_1") (pintype "passive"))
      (node (ref "R39") (pin "2") (pinfunction "2_2") (pintype "passive"))
      (node (ref "SW1") (pin "1") (pinfunction "1_1") (pintype "passive"))
    )
    (net (code "79") (name "Net-(IC8A-CK)") (class "Default")
      (node (ref "IC8") (pin "1") (pinfunction "CK_1") (pintype "input"))
      (node (ref "R44") (pin "2") (pinfunction "2_2") (pintype "passive"))
    )
    (net (code "80") (name "Net-(IC8A-Q)") (class "Default")
      (node (ref "IC8") (pin "5") (pinfunction "Q_5") (pintype "output"))
      (node (ref "R43") (pin "1") (pinfunction "1_1") (pintype "passive"))
    )
    (net (code "81") (name "Net-(IC9-OUT)") (class "Default")
      (node (ref "IC9") (pin "5") (pinfunction "OUT_5") (pintype "output"))
      (node (ref "R44") (pin "1") (pinfunction "1_1") (pintype "passive"))
    )
    (net (code "82") (name "Net-(IC10-OUT)") (class "Default")
      (node (ref "IC10") (pin "1") (pinfunction "REF_1") (pintype "input"))
      (node (ref "IC10") (pin "3") (pinfunction "OUT_3") (pintype "bidirectional"))
      (node (ref "R21") (pin "2") (pinfunction "2_2") (pintype "passive"))
      (node (ref "R22") (pin "1") (pinfunction "1_1") (pintype "passive"))
    )
    (net (code "83") (name "Net-(R40-Pad2)") (class "Default")
      (node (ref "R40") (pin "2") (pinfunction "2_2") (pintype "passive"))
      (node (ref "SW1") (pin "3") (pinfunction "3_3") (pintype "passive"))
    )
    (net (code "84") (name "V+") (class "Default")
      (node (ref "C18") (pin "1") (pinfunction "1_1") (pintype "passive"))
      (node (ref "C23") (pin "1") (pinfunction "1_1") (pintype "passive"))
      (node (ref "CON1") (pin "3") (pinfunction "3_3") (pintype "passive"))
      (node (ref "CON1") (pin "4") (pinfunction "4_4") (pintype "passive"))
      (node (ref "IC11") (pin "3") (pinfunction "IN_3") (pintype "power_in"))
      (node (ref "IC6") (pin "1") (pinfunction "IN_1") (pintype "power_in"))
      (node (ref "IC6") (pin "4") (pinfunction "IN_4") (pintype "power_in"))
    )
    (net (code "85") (name "V-") (class "Default")
      (node (ref "C24") (pin "2") (pinfunction "2_2") (pintype "passive"))
      (node (ref "CON1") (pin "1") (pinfunction "1_1") (pintype "passive"))
      (node (ref "CON1") (pin "2") (pinfunction "2_2") (pintype "passive"))
      (node (ref "IC12") (pin "2") (pinfunction "IN_2") (pintype "input"))
    )
    (net (code "86") (name "unconnected-(CON1-Pad34)") (class "Default")
      (node (ref "CON1") (pin "34") (pinfunction "34_34") (pintype "passive"))
    )
    (net (code "87") (name "unconnected-(IC3A-OUT5-Pad14)") (class "Default")
      (node (ref "IC3") (pin "14") (pinfunction "OUT5_14") (pintype "output"))
    )
    (net (code "88") (name "unconnected-(IC3A-OUT6-Pad13)") (class "Default")
      (node (ref "IC3") (pin "13") (pinfunction "OUT6_13") (pintype "output"))
    )
    (net (code "89") (name "unconnected-(IC3A-OUT7-Pad12)") (class "Default")
      (node (ref "IC3") (pin "12") (pinfunction "OUT7_12") (pintype "output"))
    )
  )
)
